# nitinolDriver.net
KiCad netlist of a schematic drawn in EAGLE
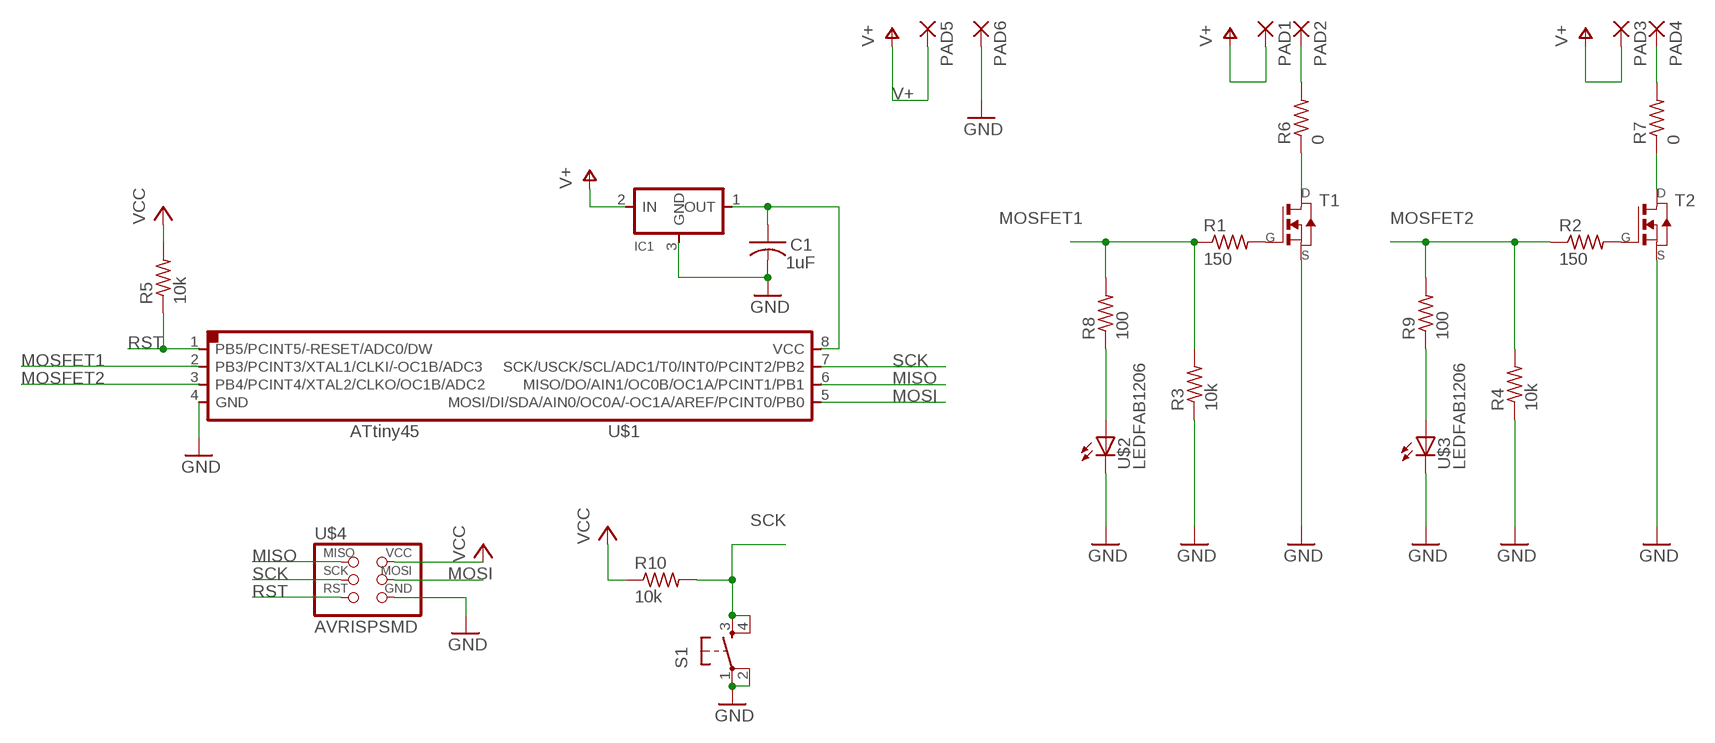
[diagram p0: schematic, sheet 1]

(export (version "E")
  (design (tool "Eeschema 10.0.6"))
  (components
    (comp (ref "C1")
      (value "1uF")
      (footprint "eagle-import:C1206FAB")
      (libsource (lib "eagle-import") (part "CAP-US1206FAB"))
    )
    (comp (ref "IC1")
      (value "REGULATORSOT23")
      (footprint "eagle-import:SOT23")
      (libsource (lib "eagle-import") (part "REGULATORSOT23"))
    )
    (comp (ref "PAD1")
      (value "2,15/1,0")
      (footprint "eagle-import:2,15_1,0")
      (libsource (lib "eagle-import") (part "2,15/1,0"))
    )
    (comp (ref "PAD2")
      (value "2,15/1,0")
      (footprint "eagle-import:2,15_1,0")
      (libsource (lib "eagle-import") (part "2,15/1,0"))
    )
    (comp (ref "PAD3")
      (value "2,15/1,0")
      (footprint "eagle-import:2,15_1,0")
      (libsource (lib "eagle-import") (part "2,15/1,0"))
    )
    (comp (ref "PAD4")
      (value "2,15/1,0")
      (footprint "eagle-import:2,15_1,0")
      (libsource (lib "eagle-import") (part "2,15/1,0"))
    )
    (comp (ref "PAD5")
      (value "2,15/1,0")
      (footprint "eagle-import:2,15_1,0")
      (libsource (lib "eagle-import") (part "2,15/1,0"))
    )
    (comp (ref "PAD6")
      (value "2,15/1,0")
      (footprint "eagle-import:2,15_1,0")
      (libsource (lib "eagle-import") (part "2,15/1,0"))
    )
    (comp (ref "R1")
      (value "150")
      (footprint "eagle-import:R1206FAB")
      (libsource (lib "eagle-import") (part "RES-US1206FAB"))
    )
    (comp (ref "R2")
      (value "150")
      (footprint "eagle-import:R1206FAB")
      (libsource (lib "eagle-import") (part "RES-US1206FAB"))
    )
    (comp (ref "R3")
      (value "10k")
      (footprint "eagle-import:R1206FAB")
      (libsource (lib "eagle-import") (part "RES-US1206FAB"))
    )
    (comp (ref "R4")
      (value "10k")
      (footprint "eagle-import:R1206FAB")
      (libsource (lib "eagle-import") (part "RES-US1206FAB"))
    )
    (comp (ref "R5")
      (value "10k")
      (footprint "eagle-import:R1206FAB")
      (libsource (lib "eagle-import") (part "RES-US1206FAB"))
    )
    (comp (ref "R6")
      (value "0")
      (footprint "eagle-import:R1206FAB")
      (libsource (lib "eagle-import") (part "RES-US1206FAB"))
    )
    (comp (ref "R7")
      (value "0")
      (footprint "eagle-import:R1206FAB")
      (libsource (lib "eagle-import") (part "RES-US1206FAB"))
    )
    (comp (ref "R8")
      (value "100")
      (footprint "eagle-import:R1206FAB")
      (libsource (lib "eagle-import") (part "RES-US1206FAB"))
    )
    (comp (ref "R9")
      (value "100")
      (footprint "eagle-import:R1206FAB")
      (libsource (lib "eagle-import") (part "RES-US1206FAB"))
    )
    (comp (ref "R10")
      (value "10k")
      (footprint "eagle-import:R1206FAB")
      (libsource (lib "eagle-import") (part "RES-US1206FAB"))
    )
    (comp (ref "S1")
      (value "6MM_SWITCH6MM_SWITCH")
      (footprint "eagle-import:6MM_SWITCH")
      (libsource (lib "eagle-import") (part "6MM_SWITCH6MM_SWITCH"))
    )
    (comp (ref "T1")
      (value "NMOSFETSOT23")
      (footprint "eagle-import:SOT-23")
      (libsource (lib "eagle-import") (part "NMOSFETSOT23"))
    )
    (comp (ref "T2")
      (value "NMOSFETSOT23")
      (footprint "eagle-import:SOT-23")
      (libsource (lib "eagle-import") (part "NMOSFETSOT23"))
    )
    (comp (ref "U$1")
      (value "ATTINY45SI")
      (footprint "eagle-import:SOIC8")
      (libsource (lib "eagle-import") (part "ATTINY45SI"))
    )
    (comp (ref "U$2")
      (value "LEDFAB1206")
      (footprint "eagle-import:LED1206FAB")
      (libsource (lib "eagle-import") (part "LEDFAB1206"))
    )
    (comp (ref "U$3")
      (value "LEDFAB1206")
      (footprint "eagle-import:LED1206FAB")
      (libsource (lib "eagle-import") (part "LEDFAB1206"))
    )
    (comp (ref "U$4")
      (value "AVRISPSMD")
      (footprint "eagle-import:2X03SMD")
      (libsource (lib "eagle-import") (part "AVRISPSMD"))
    )
  )
  (nets
    (net (code "1") (name "/MISO") (class "Default")
      (node (ref "U$1") (pin "6") (pinfunction "MISO/DO/AIN1/OC0B/OC1A/PCINT1/PB1_6") (pintype "bidirectional"))
      (node (ref "U$4") (pin "1") (pinfunction "MISO_1") (pintype "passive"))
    )
    (net (code "2") (name "/MOSFET1") (class "Default")
      (node (ref "R1") (pin "1") (pinfunction "1_1") (pintype "passive"))
      (node (ref "R3") (pin "2") (pinfunction "2_2") (pintype "passive"))
      (node (ref "R8") (pin "2") (pinfunction "2_2") (pintype "passive"))
      (node (ref "U$1") (pin "2") (pinfunction "PB3/PCINT3/XTAL1/CLKI/-OC1B/ADC3_2") (pintype "bidirectional"))
    )
    (net (code "3") (name "/MOSFET2") (class "Default")
      (node (ref "R2") (pin "1") (pinfunction "1_1") (pintype "passive"))
      (node (ref "R4") (pin "2") (pinfunction "2_2") (pintype "passive"))
      (node (ref "R9") (pin "2") (pinfunction "2_2") (pintype "passive"))
      (node (ref "U$1") (pin "3") (pinfunction "PB4/PCINT4/XTAL2/CLKO/OC1B/ADC2_3") (pintype "bidirectional"))
    )
    (net (code "4") (name "/MOSI") (class "Default")
      (node (ref "U$1") (pin "5") (pinfunction "MOSI/DI/SDA/AIN0/OC0A/-OC1A/AREF/PCINT0/PB0_5") (pintype "bidirectional"))
      (node (ref "U$4") (pin "4") (pinfunction "MOSI_4") (pintype "passive"))
    )
    (net (code "5") (name "/RST") (class "Default")
      (node (ref "R5") (pin "1") (pinfunction "1_1") (pintype "passive"))
      (node (ref "U$1") (pin "1") (pinfunction "PB5/PCINT5/-RESET/ADC0/DW_1") (pintype "bidirectional"))
      (node (ref "U$4") (pin "5") (pinfunction "RST_5") (pintype "passive"))
    )
    (net (code "6") (name "/SCK") (class "Default")
      (node (ref "R10") (pin "2") (pinfunction "2_2") (pintype "passive"))
      (node (ref "S1") (pin "3") (pinfunction "S_3") (pintype "passive"))
      (node (ref "S1") (pin "4") (pinfunction "S1_4") (pintype "passive"))
      (node (ref "U$1") (pin "7") (pinfunction "SCK/USCK/SCL/ADC1/T0/INT0/PCINT2/PB2_7") (pintype "bidirectional"))
      (node (ref "U$4") (pin "3") (pinfunction "SCK_3") (pintype "passive"))
    )
    (net (code "7") (name "GND") (class "Default")
      (node (ref "C1") (pin "2") (pinfunction "2_2") (pintype "passive"))
      (node (ref "IC1") (pin "3") (pinfunction "GND_3") (pintype "bidirectional"))
      (node (ref "PAD6") (pin "1") (pinfunction "P_1") (pintype "passive"))
      (node (ref "R3") (pin "1") (pinfunction "1_1") (pintype "passive"))
      (node (ref "R4") (pin "1") (pinfunction "1_1") (pintype "passive"))
      (node (ref "S1") (pin "1") (pinfunction "P_1") (pintype "passive"))
      (node (ref "S1") (pin "2") (pinfunction "P1_2") (pintype "passive"))
      (node (ref "T1") (pin "2") (pinfunction "S_2") (pintype "passive"))
      (node (ref "T2") (pin "2") (pinfunction "S_2") (pintype "passive"))
      (node (ref "U$1") (pin "4") (pinfunction "GND_4") (pintype "bidirectional"))
      (node (ref "U$2") (pin "2") (pinfunction "C_2") (pintype "passive"))
      (node (ref "U$3") (pin "2") (pinfunction "C_2") (pintype "passive"))
      (node (ref "U$4") (pin "6") (pinfunction "GND_6") (pintype "passive"))
    )
    (net (code "8") (name "Net-(PAD2-P)") (class "Default")
      (node (ref "PAD2") (pin "1") (pinfunction "P_1") (pintype "passive"))
      (node (ref "R6") (pin "2") (pinfunction "2_2") (pintype "passive"))
    )
    (net (code "9") (name "Net-(PAD4-P)") (class "Default")
      (node (ref "PAD4") (pin "1") (pinfunction "P_1") (pintype "passive"))
      (node (ref "R7") (pin "2") (pinfunction "2_2") (pintype "passive"))
    )
    (net (code "10") (name "Net-(T1-D)") (class "Default")
      (node (ref "R6") (pin "1") (pinfunction "1_1") (pintype "passive"))
      (node (ref "T1") (pin "1") (pinfunction "D_1") (pintype "passive"))
    )
    (net (code "11") (name "Net-(T1-G)") (class "Default")
      (node (ref "R1") (pin "2") (pinfunction "2_2") (pintype "passive"))
      (node (ref "T1") (pin "3") (pinfunction "G_3") (pintype "passive"))
    )
    (net (code "12") (name "Net-(T2-D)") (class "Default")
      (node (ref "R7") (pin "1") (pinfunction "1_1") (pintype "passive"))
      (node (ref "T2") (pin "1") (pinfunction "D_1") (pintype "passive"))
    )
    (net (code "13") (name "Net-(T2-G)") (class "Default")
      (node (ref "R2") (pin "2") (pinfunction "2_2") (pintype "passive"))
      (node (ref "T2") (pin "3") (pinfunction "G_3") (pintype "passive"))
    )
    (net (code "14") (name "Net-(U$2-A)") (class "Default")
      (node (ref "R8") (pin "1") (pinfunction "1_1") (pintype "passive"))
      (node (ref "U$2") (pin "1") (pinfunction "A_1") (pintype "passive"))
    )
    (net (code "15") (name "Net-(U$3-A)") (class "Default")
      (node (ref "R9") (pin "1") (pinfunction "1_1") (pintype "passive"))
      (node (ref "U$3") (pin "1") (pinfunction "A_1") (pintype "passive"))
    )
    (net (code "16") (name "V+") (class "Default")
      (node (ref "IC1") (pin "2") (pinfunction "IN_2") (pintype "bidirectional"))
      (node (ref "PAD1") (pin "1") (pinfunction "P_1") (pintype "passive"))
      (node (ref "PAD3") (pin "1") (pinfunction "P_1") (pintype "passive"))
      (node (ref "PAD5") (pin "1") (pinfunction "P_1") (pintype "passive"))
    )
    (net (code "17") (name "VCC") (class "Default")
      (node (ref "C1") (pin "1") (pinfunction "1_1") (pintype "passive"))
      (node (ref "IC1") (pin "1") (pinfunction "OUT_1") (pintype "bidirectional"))
      (node (ref "R10") (pin "1") (pinfunction "1_1") (pintype "passive"))
      (node (ref "R5") (pin "2") (pinfunction "2_2") (pintype "passive"))
      (node (ref "U$1") (pin "8") (pinfunction "VCC_8") (pintype "bidirectional"))
      (node (ref "U$4") (pin "2") (pinfunction "VCC_2") (pintype "passive"))
    )
  )
)
